# Controller.net
KiCad netlist of a schematic drawn in Altium Designer
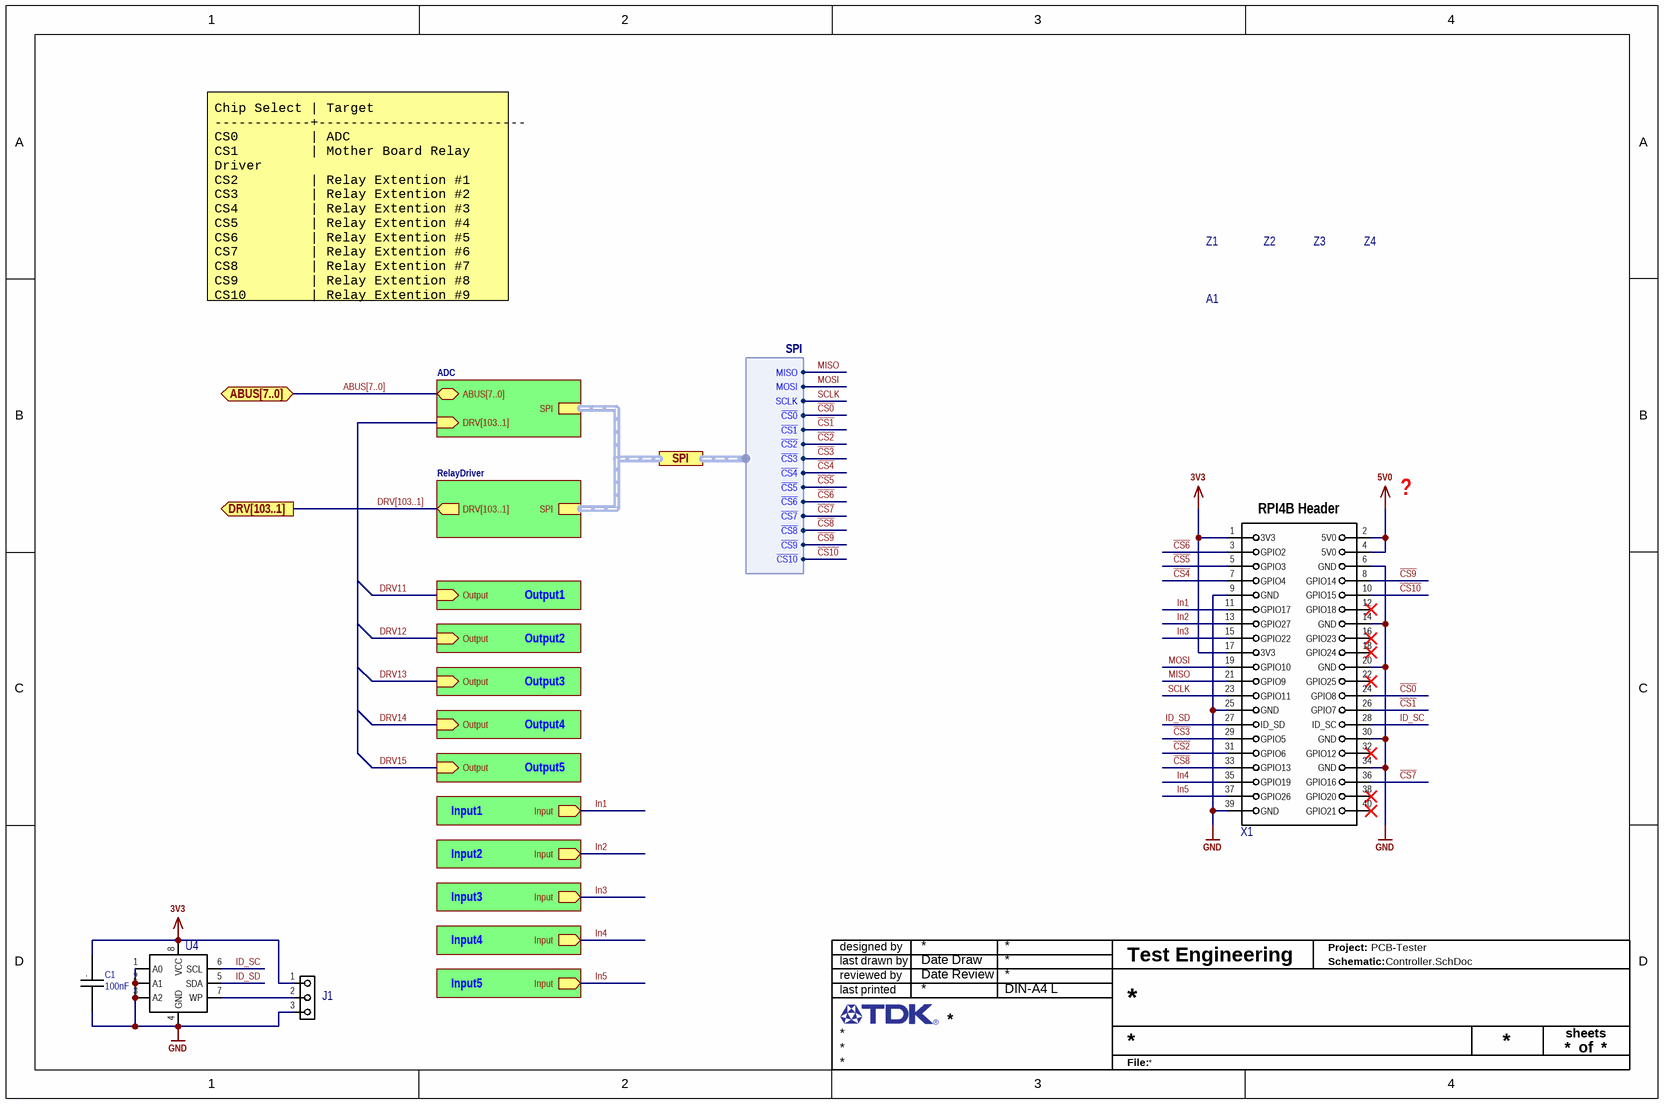
[diagram p0: Controller.SchDoc]

(export (version "E")
  (design (tool "Eeschema 10.0.6"))
  (components
    (comp (ref "A1")
      (value "A")
      (footprint "RPI4B")
      (description "RASPBERRY PI 4 MODEL B 4GB SDRAM")
      (fields
        (field (name "02. DISTRIBUTOR PART NUMBER") "1690-RASPBERRYPI4B/4GB-ND")
        (field (name "13. CREATED DATE/NAME") "??? / Hören")
      )
      (libsource (lib "Connectors") (part "RPI4B"))
    )
    (comp (ref "C1")
      (value "100nF")
      (footprint "C0402 Reflow")
      (description "Capacitor Unpolarized")
      (fields
        (field (name "TOLERANCE") "±20%")
        (field (name "Comment") "C")
        (field (name "13. CREATED DATE/NAME") "AUG2018/Hören")
      )
      (libsource (lib "chickenfood") (part "C"))
    )
    (comp (ref "J1")
      (value "J")
      (footprint "Header 100mil 3x1")
      (description "CONN HEADER VERT 3POS 2.54MM")
      (fields
        (field (name "02. DISTRIBUTOR PART NUMBER") "HMTSW-103-07-G-S-240")
        (field (name "13. CREATED DATE/NAME") "AUG2018/Hören")
      )
      (libsource (lib "chickenfood") (part "Header 3Pins 100mil"))
    )
    (comp (ref "U4")
      (value "U")
      (footprint "SOIC8 (R-8)")
      (description "IC EEPROM 256K I2C 400KHZ 8SOIC")
      (fields
        (field (name "02. DISTRIBUTOR PART NUMBER") "24LC256T-I/SNDKR-ND")
        (field (name "07. MANUFACTURER  PART NUMBER") "24LC256T-I/SN")
        (field (name "13. CREATED DATE/NAME") "AUG 2018 / Hören")
      )
      (libsource (lib "tom") (part "24LC256T-I/SN"))
    )
    (comp (ref "X1")
      (value "X")
      (footprint "RPI4B Footprint")
      (description "40 Position Elevated Socket Connector  Through Hole")
      (fields
        (field (name "02. DISTRIBUTOR PART NUMBER") "ESW-120-23-L-D-LL")
        (field (name "13. CREATED DATE/NAME") "??? / Hören")
      )
      (libsource (lib "Connectors") (part "RPI4B Footprint"))
    )
    (comp (ref "Z1")
      (value "Z")
      (footprint "HSM2.5-6.4-16-2")
      (description "HEX STANDOFF M2.5 BRASS 16MM")
      (fields
        (field (name "02. DISTRIBUTOR PART NUMBER") "HSM2.5-6.4-16-2-ND")
        (field (name "07. MANUFACTURER  PART NUMBER") "HSM2.5-6.4-16-2")
        (field (name "13. CREATED DATE/NAME") "??? / Hören")
      )
      (libsource (lib "Connectors") (part "HSM2.5-6.4-16-2"))
    )
    (comp (ref "Z2")
      (value "Z")
      (footprint "HSM2.5-6.4-16-2")
      (description "HEX STANDOFF M2.5 BRASS 16MM")
      (fields
        (field (name "02. DISTRIBUTOR PART NUMBER") "HSM2.5-6.4-16-2-ND")
        (field (name "07. MANUFACTURER  PART NUMBER") "HSM2.5-6.4-16-2")
        (field (name "13. CREATED DATE/NAME") "??? / Hören")
      )
      (libsource (lib "Connectors") (part "HSM2.5-6.4-16-2"))
    )
    (comp (ref "Z3")
      (value "Z")
      (footprint "HSM2.5-6.4-16-2")
      (description "HEX STANDOFF M2.5 BRASS 16MM")
      (fields
        (field (name "02. DISTRIBUTOR PART NUMBER") "HSM2.5-6.4-16-2-ND")
        (field (name "07. MANUFACTURER  PART NUMBER") "HSM2.5-6.4-16-2")
        (field (name "13. CREATED DATE/NAME") "??? / Hören")
      )
      (libsource (lib "Connectors") (part "HSM2.5-6.4-16-2"))
    )
    (comp (ref "Z4")
      (value "Z")
      (footprint "HSM2.5-6.4-16-2")
      (description "HEX STANDOFF M2.5 BRASS 16MM")
      (fields
        (field (name "02. DISTRIBUTOR PART NUMBER") "HSM2.5-6.4-16-2-ND")
        (field (name "07. MANUFACTURER  PART NUMBER") "HSM2.5-6.4-16-2")
        (field (name "13. CREATED DATE/NAME") "??? / Hören")
      )
      (libsource (lib "Connectors") (part "HSM2.5-6.4-16-2"))
    )
  )
  (nets
    (net (code "109") (name "/CS0") (class "Default")
      (node (ref "X1") (pin "24") (pinfunction "GPIO8_24") (pintype "passive"))
    )
    (net (code "110") (name "/CS1") (class "Default")
      (node (ref "X1") (pin "26") (pinfunction "GPIO7_26") (pintype "passive"))
    )
    (net (code "111") (name "/CS2") (class "Default")
      (node (ref "X1") (pin "31") (pinfunction "GPIO6_31") (pintype "passive"))
    )
    (net (code "112") (name "/CS3") (class "Default")
      (node (ref "X1") (pin "29") (pinfunction "GPIO5_29") (pintype "passive"))
    )
    (net (code "113") (name "/CS4") (class "Default")
      (node (ref "X1") (pin "7") (pinfunction "GPIO4_7") (pintype "passive"))
    )
    (net (code "114") (name "/CS5") (class "Default")
      (node (ref "X1") (pin "5") (pinfunction "GPIO3_5") (pintype "passive"))
    )
    (net (code "115") (name "/CS6") (class "Default")
      (node (ref "X1") (pin "3") (pinfunction "GPIO2_3") (pintype "passive"))
    )
    (net (code "116") (name "/CS7") (class "Default")
      (node (ref "X1") (pin "36") (pinfunction "GPIO16_36") (pintype "passive"))
    )
    (net (code "117") (name "/CS8") (class "Default")
      (node (ref "X1") (pin "33") (pinfunction "GPIO13_33") (pintype "passive"))
    )
    (net (code "118") (name "/CS9") (class "Default")
      (node (ref "X1") (pin "8") (pinfunction "GPIO14_8") (pintype "passive"))
    )
    (net (code "119") (name "/CS10") (class "Default")
      (node (ref "X1") (pin "10") (pinfunction "GPIO15_10") (pintype "passive"))
    )
    (net (code "126") (name "/ID_SC") (class "Default")
      (node (ref "U4") (pin "6") (pinfunction "SCL_6") (pintype "passive"))
      (node (ref "X1") (pin "28") (pinfunction "ID_SC_28") (pintype "passive"))
    )
    (net (code "127") (name "/ID_SD") (class "Default")
      (node (ref "U4") (pin "5") (pinfunction "SDA_5") (pintype "passive"))
      (node (ref "X1") (pin "27") (pinfunction "ID_SD_27") (pintype "passive"))
    )
    (net (code "128") (name "/In1") (class "Default")
      (node (ref "X1") (pin "11") (pinfunction "GPIO17_11") (pintype "passive"))
    )
    (net (code "129") (name "/In2") (class "Default")
      (node (ref "X1") (pin "13") (pinfunction "GPIO27_13") (pintype "passive"))
    )
    (net (code "130") (name "/In3") (class "Default")
      (node (ref "X1") (pin "15") (pinfunction "GPIO22_15") (pintype "passive"))
    )
    (net (code "131") (name "/In4") (class "Default")
      (node (ref "X1") (pin "35") (pinfunction "GPIO19_35") (pintype "passive"))
    )
    (net (code "132") (name "/In5") (class "Default")
      (node (ref "X1") (pin "37") (pinfunction "GPIO26_37") (pintype "passive"))
    )
    (net (code "133") (name "/MISO") (class "Default")
      (node (ref "X1") (pin "21") (pinfunction "GPIO9_21") (pintype "passive"))
    )
    (net (code "134") (name "/MOSI") (class "Default")
      (node (ref "X1") (pin "19") (pinfunction "GPIO10_19") (pintype "passive"))
    )
    (net (code "135") (name "/SCLK") (class "Default")
      (node (ref "X1") (pin "23") (pinfunction "GPIO11_23") (pintype "passive"))
    )
    (net (code "137") (name "3V3") (class "Default")
      (node (ref "C1") (pin "1") (pinfunction "1_1") (pintype "passive"))
      (node (ref "J1") (pin "1") (pinfunction "1_1") (pintype "passive"))
      (node (ref "U4") (pin "8") (pinfunction "VCC_8") (pintype "power_in"))
      (node (ref "X1") (pin "1") (pinfunction "3V3_1") (pintype "passive"))
      (node (ref "X1") (pin "17") (pinfunction "3V3_17") (pintype "passive"))
    )
    (net (code "138") (name "5V0") (class "Default")
      (node (ref "X1") (pin "2") (pinfunction "5V0_2") (pintype "passive"))
      (node (ref "X1") (pin "4") (pinfunction "5V0_4") (pintype "passive"))
    )
    (net (code "139") (name "GND") (class "Default")
      (node (ref "C1") (pin "2") (pinfunction "2_2") (pintype "passive"))
      (node (ref "J1") (pin "3") (pinfunction "3_3") (pintype "passive"))
      (node (ref "U4") (pin "1") (pinfunction "A0_1") (pintype "passive"))
      (node (ref "U4") (pin "2") (pinfunction "A1_2") (pintype "passive"))
      (node (ref "U4") (pin "3") (pinfunction "A2_3") (pintype "passive"))
      (node (ref "U4") (pin "4") (pinfunction "GND_4") (pintype "power_in"))
      (node (ref "X1") (pin "14") (pinfunction "GND_14") (pintype "passive"))
      (node (ref "X1") (pin "20") (pinfunction "GND_20") (pintype "passive"))
      (node (ref "X1") (pin "25") (pinfunction "GND_25") (pintype "passive"))
      (node (ref "X1") (pin "30") (pinfunction "GND_30") (pintype "passive"))
      (node (ref "X1") (pin "34") (pinfunction "GND_34") (pintype "passive"))
      (node (ref "X1") (pin "39") (pinfunction "GND_39") (pintype "passive"))
      (node (ref "X1") (pin "6") (pinfunction "GND_6") (pintype "passive"))
      (node (ref "X1") (pin "9") (pinfunction "GND_9") (pintype "passive"))
    )
    (net (code "140") (name "Net-(U4-WP)") (class "Default")
      (node (ref "J1") (pin "2") (pinfunction "2_2") (pintype "passive"))
      (node (ref "U4") (pin "7") (pinfunction "WP_7") (pintype "passive"))
    )
    (net (code "141") (name "unconnected-(X1-GPIO12-Pad32)") (class "Default")
      (node (ref "X1") (pin "32") (pinfunction "GPIO12_32") (pintype "passive+no_connect"))
    )
    (net (code "142") (name "unconnected-(X1-GPIO18-Pad12)") (class "Default")
      (node (ref "X1") (pin "12") (pinfunction "GPIO18_12") (pintype "passive+no_connect"))
    )
    (net (code "143") (name "unconnected-(X1-GPIO20-Pad38)") (class "Default")
      (node (ref "X1") (pin "38") (pinfunction "GPIO20_38") (pintype "passive+no_connect"))
    )
    (net (code "144") (name "unconnected-(X1-GPIO21-Pad40)") (class "Default")
      (node (ref "X1") (pin "40") (pinfunction "GPIO21_40") (pintype "passive+no_connect"))
    )
    (net (code "145") (name "unconnected-(X1-GPIO23-Pad16)") (class "Default")
      (node (ref "X1") (pin "16") (pinfunction "GPIO23_16") (pintype "passive+no_connect"))
    )
    (net (code "146") (name "unconnected-(X1-GPIO24-Pad18)") (class "Default")
      (node (ref "X1") (pin "18") (pinfunction "GPIO24_18") (pintype "passive+no_connect"))
    )
    (net (code "147") (name "unconnected-(X1-GPIO25-Pad22)") (class "Default")
      (node (ref "X1") (pin "22") (pinfunction "GPIO25_22") (pintype "passive+no_connect"))
    )
  )
)
